# dsau-adc.net
KiCad netlist of a schematic drawn in Altium Designer
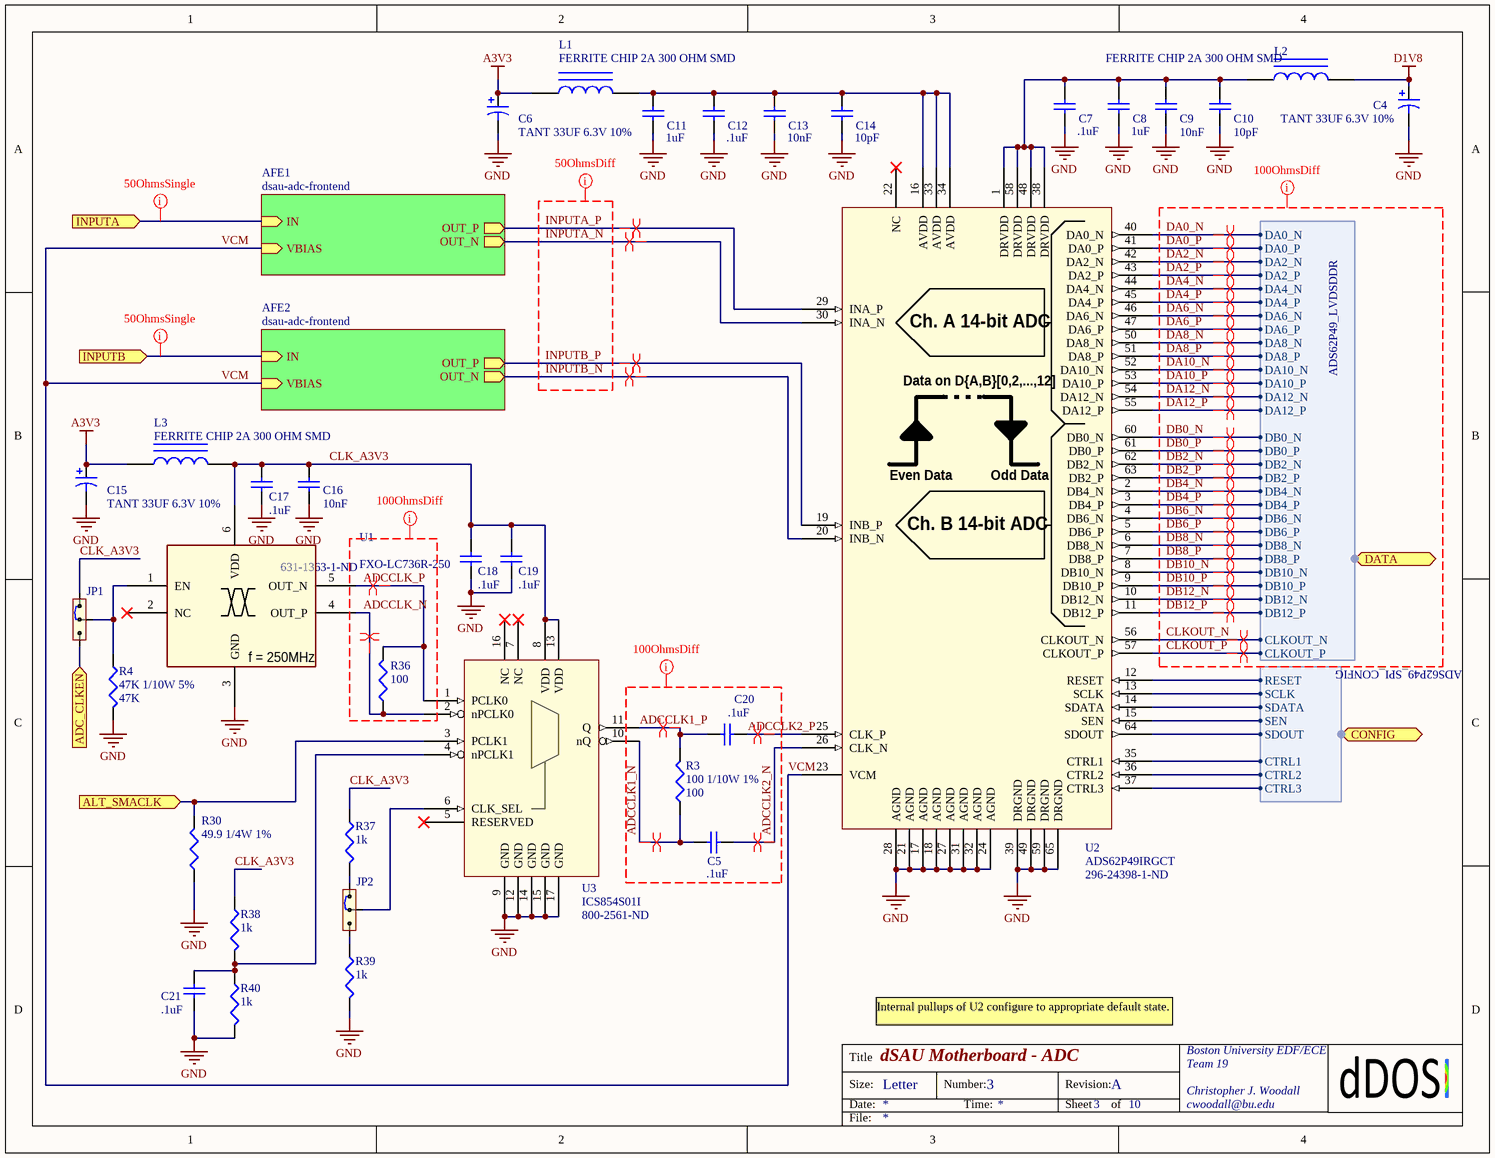
[diagram p0: dsau-adc.SchDoc]

(export (version "E")
  (design (tool "Eeschema 10.0.6"))
  (components
    (comp (ref "C4")
      (value "TANT 33UF 6.3V 10%")
      (footprint "CAPC2012L")
      (description "Polarized Capacitor (Surface Mount)")
      (fields
        (field (name "MANUFACTURER") "AVX Corporation")
        (field (name "MANUFACTURER PART NUMBER") "TPSA336K006R0600")
        (field (name "PUBLISHER") "Altium Limited")
      )
      (libsource (lib "Miscellaneous Devices") (part "Cap Pol3"))
    )
    (comp (ref "C5")
      (value ".1uF")
      (footprint "CAPC1608L")
      (description "Capacitor")
      (fields
        (field (name "MANUFACTURER") "Yageo")
        (field (name "MANUFACTURER PART NUMBER") "CC0603ZRY5V9BB104")
        (field (name "PUBLISHER") "Altium Limited")
      )
      (libsource (lib "Miscellaneous Devices") (part "Cap"))
    )
    (comp (ref "C6")
      (value "TANT 33UF 6.3V 10%")
      (footprint "CAPC2012L")
      (description "Polarized Capacitor (Surface Mount)")
      (fields
        (field (name "MANUFACTURER") "AVX Corporation")
        (field (name "MANUFACTURER PART NUMBER") "TPSA336K006R0600")
        (field (name "PUBLISHER") "Altium Limited")
      )
      (libsource (lib "Miscellaneous Devices") (part "Cap Pol3"))
    )
    (comp (ref "C7")
      (value ".1uF")
      (footprint "CAPC1608L")
      (description "Capacitor")
      (fields
        (field (name "MANUFACTURER") "Yageo")
        (field (name "MANUFACTURER PART NUMBER") "CC0603ZRY5V9BB104")
        (field (name "PUBLISHER") "Altium Limited")
      )
      (libsource (lib "Miscellaneous Devices") (part "Cap"))
    )
    (comp (ref "C8")
      (value "1uF")
      (footprint "CAPC2012L")
      (description "Capacitor")
      (fields
        (field (name "MANUFACTURER") "Yageo")
        (field (name "MANUFACTURER PART NUMBER") "CC0805KKX7R7BB105")
        (field (name "PUBLISHER") "Altium Limited")
      )
      (libsource (lib "Miscellaneous Devices") (part "Cap"))
    )
    (comp (ref "C9")
      (value "10nF")
      (footprint "CAPC1608L")
      (description "Capacitor")
      (fields
        (field (name "MANUFACTURER") "Kemet")
        (field (name "MANUFACTURER PART NUMBER") "C0603C103K3GACTU")
        (field (name "PUBLISHER") "Altium Limited")
      )
      (libsource (lib "Miscellaneous Devices") (part "Cap"))
    )
    (comp (ref "C10")
      (value "10pF")
      (footprint "CAPC1608L")
      (description "Capacitor")
      (fields
        (field (name "MANUFACTURER") "Samsung Electro-Mechanics America, Inc")
        (field (name "MANUFACTURER PART NUMBER") "CL10C100JB8NCNC")
        (field (name "PUBLISHER") "Altium Limited")
      )
      (libsource (lib "Miscellaneous Devices") (part "Cap"))
    )
    (comp (ref "C11")
      (value "1uF")
      (footprint "CAPC2012L")
      (description "Capacitor")
      (fields
        (field (name "MANUFACTURER") "Yageo")
        (field (name "MANUFACTURER PART NUMBER") "CC0805KKX7R7BB105")
        (field (name "PUBLISHER") "Altium Limited")
      )
      (libsource (lib "Miscellaneous Devices") (part "Cap"))
    )
    (comp (ref "C12")
      (value ".1uF")
      (footprint "CAPC1608L")
      (description "Capacitor")
      (fields
        (field (name "MANUFACTURER") "Yageo")
        (field (name "MANUFACTURER PART NUMBER") "CC0603ZRY5V9BB104")
        (field (name "PUBLISHER") "Altium Limited")
      )
      (libsource (lib "Miscellaneous Devices") (part "Cap"))
    )
    (comp (ref "C13")
      (value "10nF")
      (footprint "CAPC1608L")
      (description "Capacitor")
      (fields
        (field (name "MANUFACTURER") "Kemet")
        (field (name "MANUFACTURER PART NUMBER") "C0603C103K3GACTU")
        (field (name "PUBLISHER") "Altium Limited")
      )
      (libsource (lib "Miscellaneous Devices") (part "Cap"))
    )
    (comp (ref "C14")
      (value "10pF")
      (footprint "CAPC1608L")
      (description "Capacitor")
      (fields
        (field (name "MANUFACTURER") "Samsung Electro-Mechanics America, Inc")
        (field (name "MANUFACTURER PART NUMBER") "CL10C100JB8NCNC")
        (field (name "PUBLISHER") "Altium Limited")
      )
      (libsource (lib "Miscellaneous Devices") (part "Cap"))
    )
    (comp (ref "C15")
      (value "TANT 33UF 6.3V 10%")
      (footprint "CAPC2012L")
      (description "Polarized Capacitor (Surface Mount)")
      (fields
        (field (name "MANUFACTURER") "AVX Corporation")
        (field (name "MANUFACTURER PART NUMBER") "TPSA336K006R0600")
        (field (name "PUBLISHER") "Altium Limited")
      )
      (libsource (lib "Miscellaneous Devices") (part "Cap Pol3"))
    )
    (comp (ref "C16")
      (value "10nF")
      (footprint "CAPC1608L")
      (description "Capacitor")
      (fields
        (field (name "MANUFACTURER") "Kemet")
        (field (name "MANUFACTURER PART NUMBER") "C0603C103K3GACTU")
        (field (name "PUBLISHER") "Altium Limited")
      )
      (libsource (lib "Miscellaneous Devices") (part "Cap"))
    )
    (comp (ref "C17")
      (value ".1uF")
      (footprint "CAPC1608L")
      (description "Capacitor")
      (fields
        (field (name "MANUFACTURER") "Yageo")
        (field (name "MANUFACTURER PART NUMBER") "CC0603ZRY5V9BB104")
        (field (name "PUBLISHER") "Altium Limited")
      )
      (libsource (lib "Miscellaneous Devices") (part "Cap"))
    )
    (comp (ref "C18")
      (value ".1uF")
      (footprint "CAPC1608L")
      (description "Capacitor")
      (fields
        (field (name "MANUFACTURER") "Yageo")
        (field (name "MANUFACTURER PART NUMBER") "CC0603ZRY5V9BB104")
        (field (name "PUBLISHER") "Altium Limited")
      )
      (libsource (lib "Miscellaneous Devices") (part "Cap"))
    )
    (comp (ref "C19")
      (value ".1uF")
      (footprint "CAPC1608L")
      (description "Capacitor")
      (fields
        (field (name "MANUFACTURER") "Yageo")
        (field (name "MANUFACTURER PART NUMBER") "CC0603ZRY5V9BB104")
        (field (name "PUBLISHER") "Altium Limited")
      )
      (libsource (lib "Miscellaneous Devices") (part "Cap"))
    )
    (comp (ref "C20")
      (value ".1uF")
      (footprint "CAPC1608L")
      (description "Capacitor")
      (fields
        (field (name "MANUFACTURER") "Yageo")
        (field (name "MANUFACTURER PART NUMBER") "CC0603ZRY5V9BB104")
        (field (name "PUBLISHER") "Altium Limited")
      )
      (libsource (lib "Miscellaneous Devices") (part "Cap"))
    )
    (comp (ref "C21")
      (value ".1uF")
      (footprint "CAPC1608L")
      (description "Capacitor")
      (fields
        (field (name "MANUFACTURER") "Yageo")
        (field (name "MANUFACTURER PART NUMBER") "CC0603ZRY5V9BB104")
        (field (name "PUBLISHER") "Altium Limited")
      )
      (libsource (lib "Miscellaneous Devices") (part "Cap"))
    )
    (comp (ref "JP1")
      (value "JUMPER_2WAY")
      (footprint "HDR1X3")
      (libsource (lib "dsau-motherboard") (part "JUMPER_2WAY"))
    )
    (comp (ref "JP2")
      (value "JUMPER_2WAY")
      (footprint "HDR1X3")
      (libsource (lib "dsau-motherboard") (part "JUMPER_2WAY"))
    )
    (comp (ref "L1")
      (value "FERRITE CHIP 2A 300 OHM SMD")
      (footprint "INDC1608L")
      (description "Magnetic-Core Inductor")
      (fields
        (field (name "MANUFACTURER") "Laird-Signal Integrity Products")
        (field (name "MANUFACTURER PART NUMBER") "MI0603L301R-10")
        (field (name "PUBLISHER") "Altium Limited")
      )
      (libsource (lib "Miscellaneous Devices") (part "Inductor Iron"))
    )
    (comp (ref "L2")
      (value "FERRITE CHIP 2A 300 OHM SMD")
      (footprint "INDC1608L")
      (description "Magnetic-Core Inductor")
      (fields
        (field (name "MANUFACTURER") "Laird-Signal Integrity Products")
        (field (name "MANUFACTURER PART NUMBER") "MI0603L301R-10")
        (field (name "PUBLISHER") "Altium Limited")
      )
      (libsource (lib "Miscellaneous Devices") (part "Inductor Iron"))
    )
    (comp (ref "L3")
      (value "FERRITE CHIP 2A 300 OHM SMD")
      (footprint "INDC1608L")
      (description "Magnetic-Core Inductor")
      (fields
        (field (name "MANUFACTURER") "Laird-Signal Integrity Products")
        (field (name "MANUFACTURER PART NUMBER") "MI0603L301R-10")
        (field (name "PUBLISHER") "Altium Limited")
      )
      (libsource (lib "Miscellaneous Devices") (part "Inductor Iron"))
    )
    (comp (ref "R3")
      (value "100 1/10W 1%")
      (footprint "RESC1608L")
      (description "Resistor")
      (fields
        (field (name "ALTIUM_VALUE") "100")
        (field (name "MANUFACTURER") "Yageo")
        (field (name "MANUFACTURER PART NUMBER") "RC0603FR-07100RL")
        (field (name "PUBLISHER") "Altium Limited")
      )
      (libsource (lib "Miscellaneous Devices") (part "Res3"))
    )
    (comp (ref "R4")
      (value "47K 1/10W 5%")
      (footprint "RESC1608L")
      (description "Resistor")
      (fields
        (field (name "ALTIUM_VALUE") "47K")
        (field (name "MANUFACTURER") "Yageo")
        (field (name "MANUFACTURER PART NUMBER") "311-47kGRCT-ND")
        (field (name "PUBLISHER") "Altium Limited")
      )
      (libsource (lib "Miscellaneous Devices") (part "Res3"))
    )
    (comp (ref "R30")
      (value "49.9 1/4W 1%")
      (footprint "RESC3216L")
      (description "Resistor")
      (fields
        (field (name "MANUFACTURER") "Panasonic Electronic Components")
        (field (name "MANUFACTURER PART NUMBER") "ERJ-8ENF49R9V")
        (field (name "PUBLISHER") "Altium Limited")
      )
      (libsource (lib "Miscellaneous Devices") (part "Res3"))
    )
    (comp (ref "R36")
      (value "100")
      (footprint "RESC1608L")
      (description "Resistor")
      (fields
        (field (name "MANUFACTURER") "Yageo")
        (field (name "MANUFACTURER PART NUMBER") "RC0603FR-07100RL")
        (field (name "PUBLISHER") "Altium Limited")
      )
      (libsource (lib "Miscellaneous Devices") (part "Res3"))
    )
    (comp (ref "R37")
      (value "1k")
      (footprint "RESC1608L")
      (description "Resistor")
      (fields
        (field (name "MANUFACTURER") "Yageo")
        (field (name "MANUFACTURER PART NUMBER") "RC0603JR-071KL")
        (field (name "PUBLISHER") "Altium Limited")
      )
      (libsource (lib "Miscellaneous Devices") (part "Res3"))
    )
    (comp (ref "R38")
      (value "1k")
      (footprint "RESC1608L")
      (description "Resistor")
      (fields
        (field (name "MANUFACTURER") "Yageo")
        (field (name "MANUFACTURER PART NUMBER") "RC0603JR-071KL")
        (field (name "PUBLISHER") "Altium Limited")
      )
      (libsource (lib "Miscellaneous Devices") (part "Res3"))
    )
    (comp (ref "R39")
      (value "1k")
      (footprint "RESC1608L")
      (description "Resistor")
      (fields
        (field (name "MANUFACTURER") "Yageo")
        (field (name "MANUFACTURER PART NUMBER") "RC0603JR-071KL")
        (field (name "PUBLISHER") "Altium Limited")
      )
      (libsource (lib "Miscellaneous Devices") (part "Res3"))
    )
    (comp (ref "R40")
      (value "1k")
      (footprint "RESC1608L")
      (description "Resistor")
      (fields
        (field (name "MANUFACTURER") "Yageo")
        (field (name "MANUFACTURER PART NUMBER") "RC0603JR-071KL")
        (field (name "PUBLISHER") "Altium Limited")
      )
      (libsource (lib "Miscellaneous Devices") (part "Res3"))
    )
    (comp (ref "U1")
      (value "FXO-LC736R-250MHz")
      (footprint "FXO-LC736R-SMD_6")
      (description "OSC 250 MHZ 3.3V LVDS SMD")
      (fields
        (field (name "SUPPLIER PART NUMBER 1") "631-1363-1-ND")
        (field (name "MANUFACTURER") "Fox Electronics")
        (field (name "MANUFACTURER PART NUMBER") "FXO-LC736R-250")
      )
      (libsource (lib "dsau-motherboard") (part "FXO-LC736R-250MHz"))
    )
    (comp (ref "U2")
      (value "ADS62P49_SINGLE")
      (footprint "VQFN-64")
      (description "IC ADC DUAL 14BIT 250MSPS 64VQFN")
      (fields
        (field (name "MANUFACTURER") "Texas Instruments")
        (field (name "MANUFACTURER PART NUMBER") "ADS62P49IRGCT")
        (field (name "SUPPLIER PART NUMBER 1") "296-24398-1-ND")
      )
      (libsource (lib "dsau-motherboard") (part "ADS62P49_SINGLE"))
    )
    (comp (ref "U3")
      (value "ICS854S01I")
      (footprint "VFQFN16_CUSTOM")
      (fields (field (name "SUPPLIER PART NUMBER 1") "800-2561-ND"))
      (libsource (lib "dsau-motherboard") (part "ICS854S01I"))
    )
  )
  (nets
    (net (code "3") (name "/ADCCLK1_N") (class "Default")
      (node (ref "C5") (pin "1") (pinfunction "1_1") (pintype "passive"))
      (node (ref "R3") (pin "1") (pinfunction "1_1") (pintype "passive"))
      (node (ref "U3") (pin "10") (pinfunction "nQ_10") (pintype "output"))
    )
    (net (code "4") (name "/ADCCLK1_P") (class "Default")
      (node (ref "C20") (pin "1") (pinfunction "1_1") (pintype "passive"))
      (node (ref "R3") (pin "2") (pinfunction "2_2") (pintype "passive"))
      (node (ref "U3") (pin "11") (pinfunction "Q_11") (pintype "output"))
    )
    (net (code "5") (name "/ADCCLK2_N") (class "Default")
      (node (ref "C5") (pin "2") (pinfunction "2_2") (pintype "passive"))
      (node (ref "U2") (pin "26") (pinfunction "CLK_N_26") (pintype "input"))
    )
    (net (code "6") (name "/ADCCLK2_P") (class "Default")
      (node (ref "C20") (pin "2") (pinfunction "2_2") (pintype "passive"))
      (node (ref "U2") (pin "25") (pinfunction "CLK_P_25") (pintype "input"))
    )
    (net (code "7") (name "/ADCCLK_N") (class "Default")
      (node (ref "R36") (pin "1") (pinfunction "1_1") (pintype "passive"))
      (node (ref "U1") (pin "4") (pinfunction "OUT_P_4") (pintype "passive"))
      (node (ref "U3") (pin "2") (pinfunction "nPCLK0_2") (pintype "input"))
    )
    (net (code "8") (name "/ADCCLK_P") (class "Default")
      (node (ref "R36") (pin "2") (pinfunction "2_2") (pintype "passive"))
      (node (ref "U1") (pin "5") (pinfunction "OUT_N_5") (pintype "passive"))
      (node (ref "U3") (pin "1") (pinfunction "PCLK0_1") (pintype "input"))
    )
    (net (code "9") (name "/ADC_CLKEN") (class "Default") (node (ref "JP1") (pin "3") (pintype "passive")))
    (net (code "10") (name "/ALT_SMACLK") (class "Default")
      (node (ref "R30") (pin "2") (pinfunction "2_2") (pintype "passive"))
      (node (ref "U3") (pin "3") (pinfunction "PCLK1_3") (pintype "input"))
    )
    (net (code "11") (name "/CLKOUT_N") (class "Default")
      (node (ref "U2") (pin "56") (pinfunction "CLKOUT_N_56") (pintype "output"))
    )
    (net (code "12") (name "/CLKOUT_P") (class "Default")
      (node (ref "U2") (pin "57") (pinfunction "CLKOUT_P_57") (pintype "output"))
    )
    (net (code "13") (name "/CLK_A3V3") (class "Default")
      (node (ref "C16") (pin "1") (pinfunction "1_1") (pintype "passive"))
      (node (ref "C17") (pin "1") (pinfunction "1_1") (pintype "passive"))
      (node (ref "C18") (pin "1") (pinfunction "1_1") (pintype "passive"))
      (node (ref "C19") (pin "1") (pinfunction "1_1") (pintype "passive"))
      (node (ref "JP1") (pin "1") (pintype "passive"))
      (node (ref "L3") (pin "1") (pinfunction "1_1") (pintype "passive"))
      (node (ref "R37") (pin "1") (pinfunction "1_1") (pintype "passive"))
      (node (ref "R38") (pin "1") (pinfunction "1_1") (pintype "passive"))
      (node (ref "U1") (pin "6") (pinfunction "VDD_6") (pintype "passive"))
      (node (ref "U3") (pin "13") (pinfunction "VDD_13") (pintype "power_in"))
      (node (ref "U3") (pin "8") (pinfunction "VDD_8") (pintype "power_in"))
    )
    (net (code "14") (name "/CTRL1") (class "Default")
      (node (ref "U2") (pin "35") (pinfunction "CTRL1_35") (pintype "input"))
    )
    (net (code "15") (name "/CTRL2") (class "Default")
      (node (ref "U2") (pin "36") (pinfunction "CTRL2_36") (pintype "input"))
    )
    (net (code "16") (name "/CTRL3") (class "Default")
      (node (ref "U2") (pin "37") (pinfunction "CTRL3_37") (pintype "input"))
    )
    (net (code "17") (name "/DA0_N") (class "Default")
      (node (ref "U2") (pin "40") (pinfunction "DA0_N_40") (pintype "output"))
    )
    (net (code "18") (name "/DA0_P") (class "Default")
      (node (ref "U2") (pin "41") (pinfunction "DA0_P_41") (pintype "output"))
    )
    (net (code "19") (name "/DA2_N") (class "Default")
      (node (ref "U2") (pin "42") (pinfunction "DA2_N_42") (pintype "output"))
    )
    (net (code "20") (name "/DA2_P") (class "Default")
      (node (ref "U2") (pin "43") (pinfunction "DA2_P_43") (pintype "output"))
    )
    (net (code "21") (name "/DA4_N") (class "Default")
      (node (ref "U2") (pin "44") (pinfunction "DA4_N_44") (pintype "output"))
    )
    (net (code "22") (name "/DA4_P") (class "Default")
      (node (ref "U2") (pin "45") (pinfunction "DA4_P_45") (pintype "output"))
    )
    (net (code "23") (name "/DA6_N") (class "Default")
      (node (ref "U2") (pin "46") (pinfunction "DA6_N_46") (pintype "output"))
    )
    (net (code "24") (name "/DA6_P") (class "Default")
      (node (ref "U2") (pin "47") (pinfunction "DA6_P_47") (pintype "output"))
    )
    (net (code "25") (name "/DA8_N") (class "Default")
      (node (ref "U2") (pin "50") (pinfunction "DA8_N_50") (pintype "output"))
    )
    (net (code "26") (name "/DA8_P") (class "Default")
      (node (ref "U2") (pin "51") (pinfunction "DA8_P_51") (pintype "output"))
    )
    (net (code "27") (name "/DA10_N") (class "Default")
      (node (ref "U2") (pin "52") (pinfunction "DA10_N_52") (pintype "output"))
    )
    (net (code "28") (name "/DA10_P") (class "Default")
      (node (ref "U2") (pin "53") (pinfunction "DA10_P_53") (pintype "output"))
    )
    (net (code "29") (name "/DA12_N") (class "Default")
      (node (ref "U2") (pin "54") (pinfunction "DA12_N_54") (pintype "output"))
    )
    (net (code "30") (name "/DA12_P") (class "Default")
      (node (ref "U2") (pin "55") (pinfunction "DA12_P_55") (pintype "output"))
    )
    (net (code "31") (name "/DB0_N") (class "Default")
      (node (ref "U2") (pin "60") (pinfunction "DB0_N_60") (pintype "output"))
    )
    (net (code "32") (name "/DB0_P") (class "Default")
      (node (ref "U2") (pin "61") (pinfunction "DB0_P_61") (pintype "output"))
    )
    (net (code "33") (name "/DB2_N") (class "Default")
      (node (ref "U2") (pin "62") (pinfunction "DB2_N_62") (pintype "output"))
    )
    (net (code "34") (name "/DB2_P") (class "Default")
      (node (ref "U2") (pin "63") (pinfunction "DB2_P_63") (pintype "output"))
    )
    (net (code "35") (name "/DB4_N") (class "Default")
      (node (ref "U2") (pin "2") (pinfunction "DB4_N_2") (pintype "output"))
    )
    (net (code "36") (name "/DB4_P") (class "Default")
      (node (ref "U2") (pin "3") (pinfunction "DB4_P_3") (pintype "output"))
    )
    (net (code "37") (name "/DB6_N") (class "Default")
      (node (ref "U2") (pin "4") (pinfunction "DB6_N_4") (pintype "output"))
    )
    (net (code "38") (name "/DB6_P") (class "Default")
      (node (ref "U2") (pin "5") (pinfunction "DB6_P_5") (pintype "output"))
    )
    (net (code "39") (name "/DB8_N") (class "Default")
      (node (ref "U2") (pin "6") (pinfunction "DB8_N_6") (pintype "output"))
    )
    (net (code "40") (name "/DB8_P") (class "Default")
      (node (ref "U2") (pin "7") (pinfunction "DB8_P_7") (pintype "output"))
    )
    (net (code "41") (name "/DB10_N") (class "Default")
      (node (ref "U2") (pin "8") (pinfunction "DB10_N_8") (pintype "output"))
    )
    (net (code "42") (name "/DB10_P") (class "Default")
      (node (ref "U2") (pin "9") (pinfunction "DB10_P_9") (pintype "output"))
    )
    (net (code "43") (name "/DB12_N") (class "Default")
      (node (ref "U2") (pin "10") (pinfunction "DB12_N_10") (pintype "output"))
    )
    (net (code "44") (name "/DB12_P") (class "Default")
      (node (ref "U2") (pin "11") (pinfunction "DB12_P_11") (pintype "output"))
    )
    (net (code "46") (name "/INPUTA_N") (class "Default")
      (node (ref "U2") (pin "30") (pinfunction "INA_N_30") (pintype "input"))
    )
    (net (code "47") (name "/INPUTA_P") (class "Default")
      (node (ref "U2") (pin "29") (pinfunction "INA_P_29") (pintype "input"))
    )
    (net (code "49") (name "/INPUTB_N") (class "Default")
      (node (ref "U2") (pin "20") (pinfunction "INB_N_20") (pintype "input"))
    )
    (net (code "50") (name "/INPUTB_P") (class "Default")
      (node (ref "U2") (pin "19") (pinfunction "INB_P_19") (pintype "input"))
    )
    (net (code "51") (name "/RESET") (class "Default")
      (node (ref "U2") (pin "12") (pinfunction "RESET_12") (pintype "input"))
    )
    (net (code "52") (name "/SCLK") (class "Default")
      (node (ref "U2") (pin "13") (pinfunction "SCLK_13") (pintype "input"))
    )
    (net (code "53") (name "/SDATA") (class "Default")
      (node (ref "U2") (pin "14") (pinfunction "SDATA_14") (pintype "input"))
    )
    (net (code "54") (name "/SDOUT") (class "Default")
      (node (ref "U2") (pin "64") (pinfunction "SDOUT_64") (pintype "output"))
    )
    (net (code "55") (name "/SEN") (class "Default")
      (node (ref "U2") (pin "15") (pinfunction "SEN_15") (pintype "input"))
    )
    (net (code "56") (name "/VCM") (class "Default")
      (node (ref "U2") (pin "23") (pinfunction "VCM_23") (pintype "passive"))
    )
    (net (code "59") (name "A3V3") (class "Default")
      (node (ref "C15") (pin "1") (pinfunction "1_1") (pintype "passive"))
      (node (ref "C6") (pin "1") (pinfunction "1_1") (pintype "passive"))
      (node (ref "L1") (pin "2") (pinfunction "2_2") (pintype "passive"))
      (node (ref "L3") (pin "2") (pinfunction "2_2") (pintype "passive"))
    )
    (net (code "60") (name "D1V8") (class "Default")
      (node (ref "C4") (pin "1") (pinfunction "1_1") (pintype "passive"))
      (node (ref "L2") (pin "1") (pinfunction "1_1") (pintype "passive"))
    )
    (net (code "61") (name "GND") (class "Default")
      (node (ref "C10") (pin "2") (pinfunction "2_2") (pintype "passive"))
      (node (ref "C11") (pin "2") (pinfunction "2_2") (pintype "passive"))
      (node (ref "C12") (pin "2") (pinfunction "2_2") (pintype "passive"))
      (node (ref "C13") (pin "2") (pinfunction "2_2") (pintype "passive"))
      (node (ref "C14") (pin "2") (pinfunction "2_2") (pintype "passive"))
      (node (ref "C15") (pin "2") (pinfunction "2_2") (pintype "passive"))
      (node (ref "C16") (pin "2") (pinfunction "2_2") (pintype "passive"))
      (node (ref "C17") (pin "2") (pinfunction "2_2") (pintype "passive"))
      (node (ref "C18") (pin "2") (pinfunction "2_2") (pintype "passive"))
      (node (ref "C19") (pin "2") (pinfunction "2_2") (pintype "passive"))
      (node (ref "C21") (pin "2") (pinfunction "2_2") (pintype "passive"))
      (node (ref "C4") (pin "2") (pinfunction "2_2") (pintype "passive"))
      (node (ref "C6") (pin "2") (pinfunction "2_2") (pintype "passive"))
      (node (ref "C7") (pin "2") (pinfunction "2_2") (pintype "passive"))
      (node (ref "C8") (pin "2") (pinfunction "2_2") (pintype "passive"))
      (node (ref "C9") (pin "2") (pinfunction "2_2") (pintype "passive"))
      (node (ref "R30") (pin "1") (pinfunction "1_1") (pintype "passive"))
      (node (ref "R39") (pin "2") (pinfunction "2_2") (pintype "passive"))
      (node (ref "R4") (pin "2") (pinfunction "2_2") (pintype "passive"))
      (node (ref "R40") (pin "2") (pinfunction "2_2") (pintype "passive"))
      (node (ref "U1") (pin "3") (pinfunction "GND_3") (pintype "passive"))
      (node (ref "U2") (pin "17") (pinfunction "AGND_17") (pintype "power_in"))
      (node (ref "U2") (pin "18") (pinfunction "AGND_18") (pintype "power_in"))
      (node (ref "U2") (pin "21") (pinfunction "AGND_21") (pintype "power_in"))
      (node (ref "U2") (pin "24") (pinfunction "AGND_24") (pintype "power_in"))
      (node (ref "U2") (pin "27") (pinfunction "AGND_27") (pintype "power_in"))
      (node (ref "U2") (pin "28") (pinfunction "AGND_28") (pintype "power_in"))
      (node (ref "U2") (pin "31") (pinfunction "AGND_31") (pintype "power_in"))
      (node (ref "U2") (pin "32") (pinfunction "AGND_32") (pintype "power_in"))
      (node (ref "U2") (pin "39") (pinfunction "DRGND_39") (pintype "power_in"))
      (node (ref "U2") (pin "49") (pinfunction "DRGND_49") (pintype "power_in"))
      (node (ref "U2") (pin "59") (pinfunction "DRGND_59") (pintype "power_in"))
      (node (ref "U2") (pin "65") (pinfunction "DRGND_65") (pintype "power_in"))
      (node (ref "U3") (pin "12") (pinfunction "GND_12") (pintype "power_in"))
      (node (ref "U3") (pin "14") (pinfunction "GND_14") (pintype "power_in"))
      (node (ref "U3") (pin "15") (pinfunction "GND_15") (pintype "power_in"))
      (node (ref "U3") (pin "17") (pinfunction "GND_17") (pintype "power_in"))
      (node (ref "U3") (pin "9") (pinfunction "GND_9") (pintype "power_in"))
    )
    (net (code "62") (name "Net-(C10-Pad1)") (class "Default")
      (node (ref "C10") (pin "1") (pinfunction "1_1") (pintype "passive"))
      (node (ref "C7") (pin "1") (pinfunction "1_1") (pintype "passive"))
      (node (ref "C8") (pin "1") (pinfunction "1_1") (pintype "passive"))
      (node (ref "C9") (pin "1") (pinfunction "1_1") (pintype "passive"))
      (node (ref "L2") (pin "2") (pinfunction "2_2") (pintype "passive"))
      (node (ref "U2") (pin "1") (pinfunction "DRVDD_1") (pintype "power_in"))
      (node (ref "U2") (pin "38") (pinfunction "DRVDD_38") (pintype "power_in"))
      (node (ref "U2") (pin "48") (pinfunction "DRVDD_48") (pintype "power_in"))
      (node (ref "U2") (pin "58") (pinfunction "DRVDD_58") (pintype "power_in"))
    )
    (net (code "63") (name "Net-(C11-Pad1)") (class "Default")
      (node (ref "C11") (pin "1") (pinfunction "1_1") (pintype "passive"))
      (node (ref "C12") (pin "1") (pinfunction "1_1") (pintype "passive"))
      (node (ref "C13") (pin "1") (pinfunction "1_1") (pintype "passive"))
      (node (ref "C14") (pin "1") (pinfunction "1_1") (pintype "passive"))
      (node (ref "L1") (pin "1") (pinfunction "1_1") (pintype "passive"))
      (node (ref "U2") (pin "16") (pinfunction "AVDD_16") (pintype "power_in"))
      (node (ref "U2") (pin "33") (pinfunction "AVDD_33") (pintype "power_in"))
      (node (ref "U2") (pin "34") (pinfunction "AVDD_34") (pintype "power_in"))
    )
    (net (code "64") (name "Net-(JP2-Pad1)") (class "Default")
      (node (ref "JP2") (pin "1") (pintype "passive"))
      (node (ref "R37") (pin "2") (pinfunction "2_2") (pintype "passive"))
    )
    (net (code "65") (name "Net-(JP2-Pad3)") (class "Default")
      (node (ref "JP2") (pin "3") (pintype "passive"))
      (node (ref "R39") (pin "1") (pinfunction "1_1") (pintype "passive"))
    )
    (net (code "66") (name "Net-(U1-EN)") (class "Default")
      (node (ref "JP1") (pin "2") (pintype "passive"))
      (node (ref "R4") (pin "1") (pinfunction "1_1") (pintype "passive"))
      (node (ref "U1") (pin "1") (pinfunction "EN_1") (pintype "passive"))
    )
    (net (code "67") (name "Net-(U3-CLK_SEL)") (class "Default")
      (node (ref "JP2") (pin "2") (pintype "passive"))
      (node (ref "U3") (pin "6") (pinfunction "CLK_SEL_6") (pintype "input"))
    )
    (net (code "68") (name "Net-(U3-nPCLK1)") (class "Default")
      (node (ref "C21") (pin "1") (pinfunction "1_1") (pintype "passive"))
      (node (ref "R38") (pin "2") (pinfunction "2_2") (pintype "passive"))
      (node (ref "R40") (pin "1") (pinfunction "1_1") (pintype "passive"))
      (node (ref "U3") (pin "4") (pinfunction "nPCLK1_4") (pintype "input"))
    )
    (net (code "69") (name "unconnected-(U1-NC-Pad2)") (class "Default")
      (node (ref "U1") (pin "2") (pinfunction "NC_2") (pintype "passive+no_connect"))
    )
    (net (code "70") (name "unconnected-(U2-NC-Pad22)") (class "Default")
      (node (ref "U2") (pin "22") (pinfunction "NC_22") (pintype "passive+no_connect"))
    )
    (net (code "71") (name "unconnected-(U3-NC-Pad7)") (class "Default")
      (node (ref "U3") (pin "7") (pinfunction "NC_7") (pintype "passive+no_connect"))
    )
    (net (code "72") (name "unconnected-(U3-NC-Pad16)") (class "Default")
      (node (ref "U3") (pin "16") (pinfunction "NC_16") (pintype "passive+no_connect"))
    )
    (net (code "73") (name "unconnected-(U3-RESERVED-Pad5)") (class "Default")
      (node (ref "U3") (pin "5") (pinfunction "RESERVED_5") (pintype "passive+no_connect"))
    )
  )
)
